# slush_cap_board_rev_a.net
KiCad netlist of a schematic drawn in EAGLE
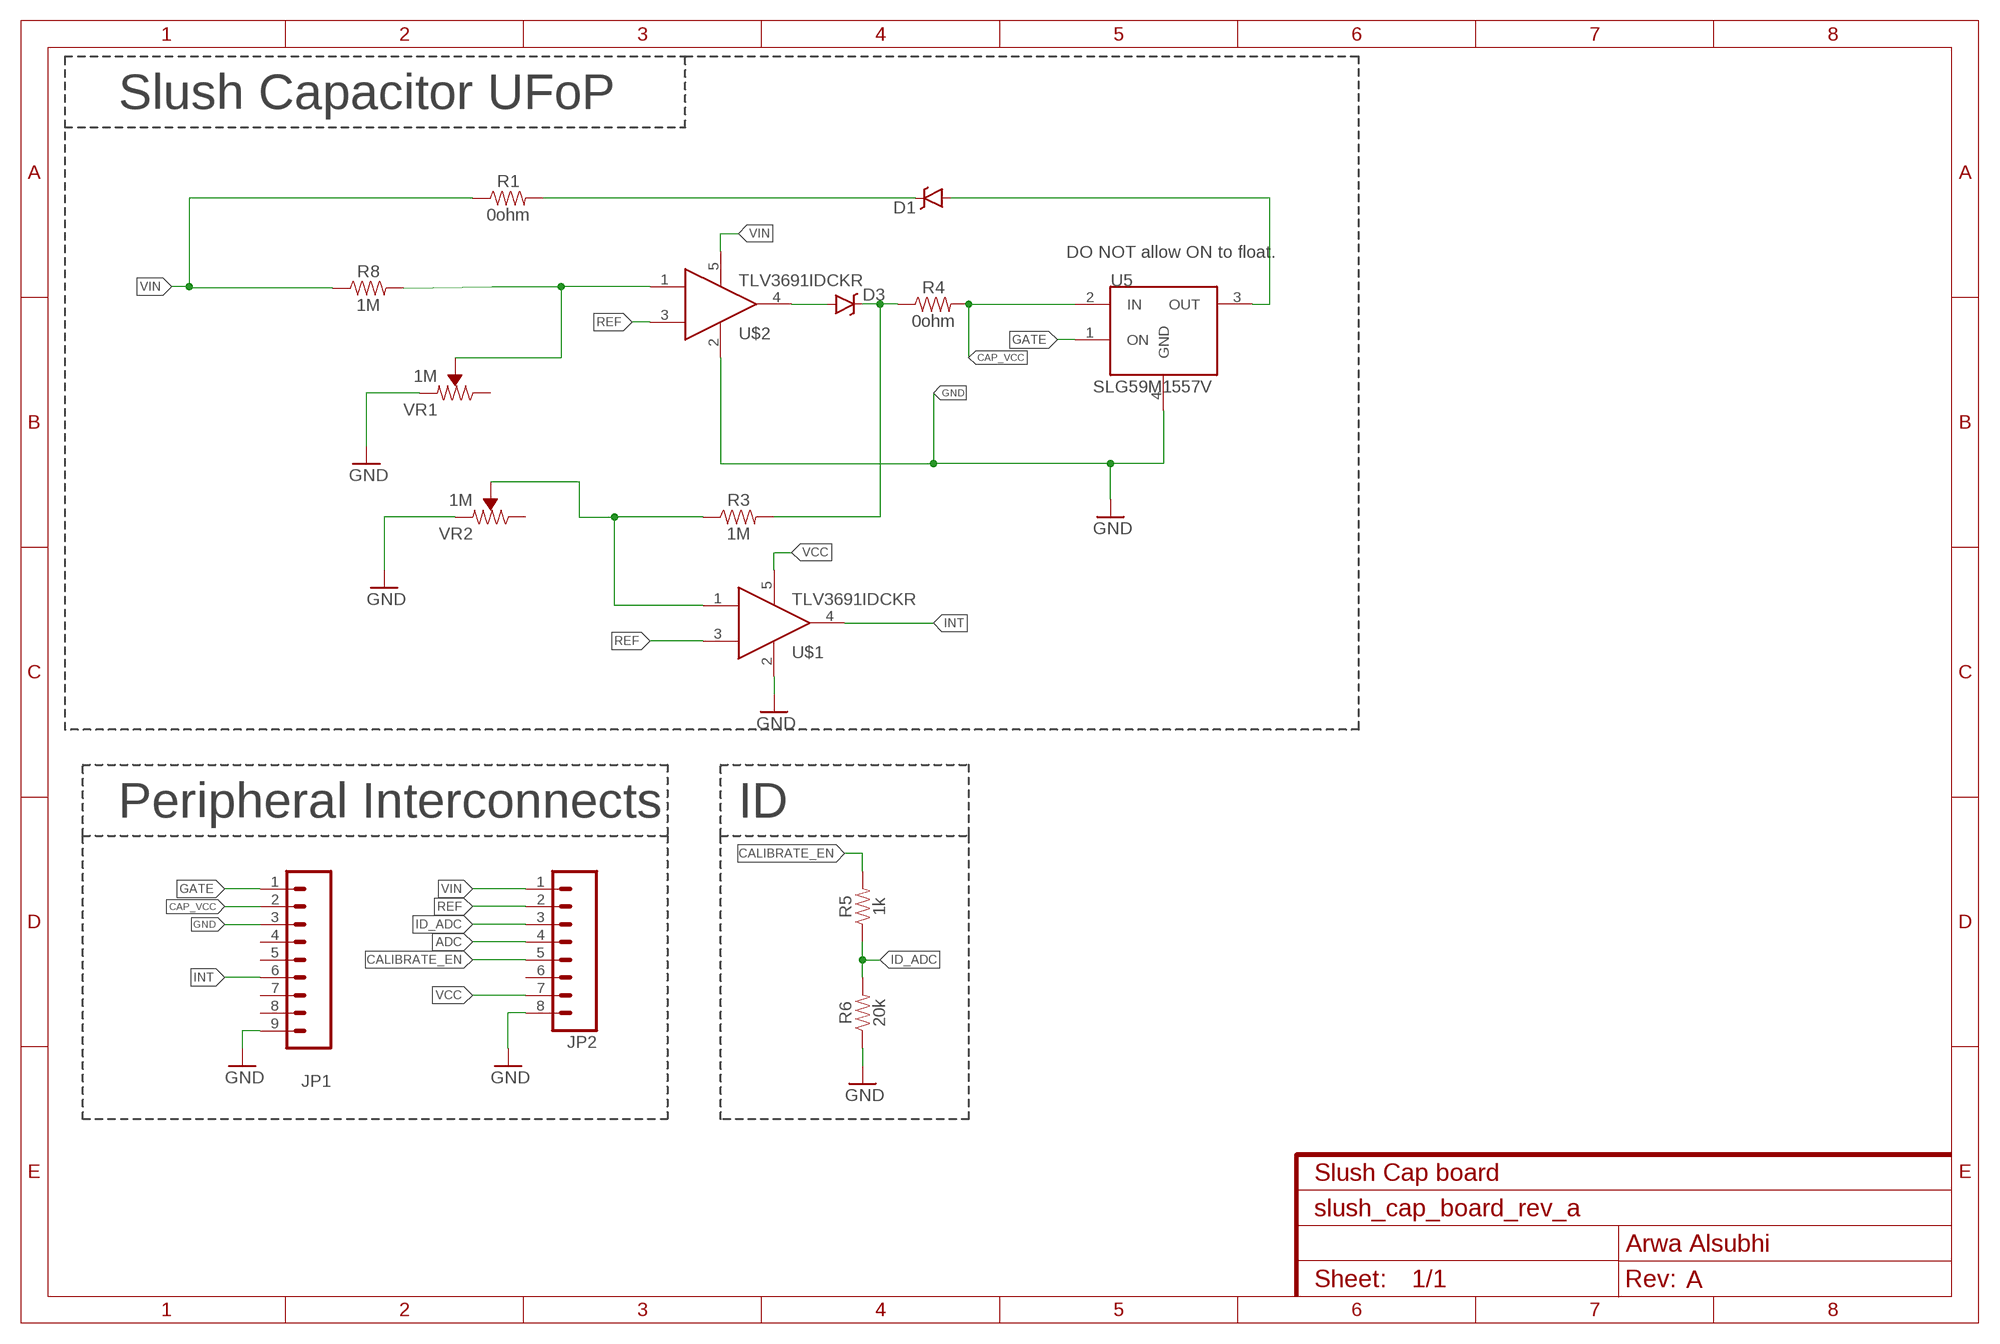
[diagram p0: schematic, sheet 1]

(export (version "E")
  (design (tool "Eeschema 10.0.6"))
  (components
    (comp (ref "D1")
      (value "RB751")
      (footprint "eagle-import:SOD-523")
      (fields (field (name "MPN") "BAS40-02V-V-G-08"))
      (libsource (lib "eagle-import") (part "DIODE-SCHOTTKY-RB751"))
    )
    (comp (ref "D3")
      (value "RB751")
      (footprint "eagle-import:SOD-523")
      (fields (field (name "MPN") "BAS40-02V-V-G-08"))
      (libsource (lib "eagle-import") (part "DIODE-SCHOTTKY-RB751"))
    )
    (comp (ref "JP1")
      (value "M091.27MM")
      (footprint "eagle-import:1X09-1.27MM")
      (fields (field (name "MANUFACTURERPARTNUMBER") "GRPB091VWVN-RC ") (field (name "MPN") "GRPB091VWVN-RC"))
      (libsource (lib "eagle-import") (part "M091.27MM"))
    )
    (comp (ref "JP2")
      (value "M081.27MM")
      (footprint "eagle-import:1X08-1.27MM")
      (fields (field (name "MANUFACTURERPARTNUMBER") "GRPB081VWVN-RC "))
      (libsource (lib "eagle-import") (part "M081.27MM"))
    )
    (comp (ref "R1")
      (value "0ohm")
      (footprint "eagle-import:0603")
      (libsource (lib "eagle-import") (part "0603-RESISTOR-0603-1/10W-1%"))
    )
    (comp (ref "R3")
      (value "1M")
      (footprint "eagle-import:0805")
      (libsource (lib "eagle-import") (part "0.3OHM-0805-1/8W-1%"))
    )
    (comp (ref "R4")
      (value "0ohm")
      (footprint "eagle-import:0603")
      (libsource (lib "eagle-import") (part "0603-RESISTOR-0603-1/10W-1%"))
    )
    (comp (ref "R5")
      (value "1k")
      (footprint "eagle-import:0603")
      (libsource (lib "eagle-import") (part "0603-RESISTOR-0603-1/10W-1%"))
    )
    (comp (ref "R6")
      (value "20k")
      (footprint "eagle-import:0603")
      (libsource (lib "eagle-import") (part "0603-RESISTOR-0603-1/10W-1%"))
    )
    (comp (ref "R8")
      (value "1M")
      (footprint "eagle-import:0805")
      (libsource (lib "eagle-import") (part "0.3OHM-0805-1/8W-1%"))
    )
    (comp (ref "U$1")
      (value "TLV3691IDCKR")
      (footprint "eagle-import:SOT353")
      (libsource (lib "eagle-import") (part "TLV3691IDCKR"))
    )
    (comp (ref "U$2")
      (value "TLV3691IDCKR")
      (footprint "eagle-import:SOT353")
      (libsource (lib "eagle-import") (part "TLV3691IDCKR"))
    )
    (comp (ref "U5")
      (value "SLG59M1557V")
      (footprint "eagle-import:4STDFN")
      (fields (field (name "MPN") "SLG59M1557V "))
      (libsource (lib "eagle-import") (part "SLG59M1557V"))
    )
    (comp (ref "VR1")
      (value "1M")
      (footprint "eagle-import:TRIMPOT-SMD-3MM-CLOSED")
      (libsource (lib "eagle-import") (part "TRIMPOT-SMD-3MM-CLOSED-1/8W-20%"))
    )
    (comp (ref "VR2")
      (value "1M")
      (footprint "eagle-import:TRIMPOT-SMD-3MM-CLOSED")
      (libsource (lib "eagle-import") (part "TRIMPOT-SMD-3MM-CLOSED-1/8W-20%"))
    )
  )
  (nets
    (net (code "1") (name "ADC") (class "Default")
      (node (ref "JP2") (pin "4") (pinfunction "4_4") (pintype "passive"))
    )
    (net (code "2") (name "CALIBRATE_EN") (class "Default")
      (node (ref "JP2") (pin "5") (pinfunction "5_5") (pintype "passive"))
      (node (ref "R5") (pin "2") (pinfunction "2_2") (pintype "passive"))
    )
    (net (code "3") (name "CAP_VCC") (class "Default")
      (node (ref "JP1") (pin "2") (pinfunction "2_2") (pintype "passive"))
      (node (ref "R4") (pin "2") (pinfunction "2_2") (pintype "passive"))
      (node (ref "U5") (pin "2") (pinfunction "IN_2") (pintype "bidirectional"))
    )
    (net (code "4") (name "GATE") (class "Default")
      (node (ref "JP1") (pin "1") (pinfunction "1_1") (pintype "passive"))
      (node (ref "U5") (pin "1") (pinfunction "ON_1") (pintype "bidirectional"))
    )
    (net (code "5") (name "GND") (class "Default")
      (node (ref "JP1") (pin "3") (pinfunction "3_3") (pintype "passive"))
      (node (ref "JP1") (pin "9") (pinfunction "9_9") (pintype "passive"))
      (node (ref "JP2") (pin "8") (pinfunction "8_8") (pintype "passive"))
      (node (ref "R6") (pin "1") (pinfunction "1_1") (pintype "passive"))
      (node (ref "U$1") (pin "2") (pinfunction "2_2") (pintype "bidirectional"))
      (node (ref "U$2") (pin "2") (pinfunction "2_2") (pintype "bidirectional"))
      (node (ref "U5") (pin "4") (pinfunction "GND_4") (pintype "bidirectional"))
      (node (ref "VR1") (pin "1") (pinfunction "CCW_1") (pintype "passive"))
      (node (ref "VR2") (pin "1") (pinfunction "CCW_1") (pintype "passive"))
    )
    (net (code "6") (name "ID_ADC") (class "Default")
      (node (ref "JP2") (pin "3") (pinfunction "3_3") (pintype "passive"))
      (node (ref "R5") (pin "1") (pinfunction "1_1") (pintype "passive"))
      (node (ref "R6") (pin "2") (pinfunction "2_2") (pintype "passive"))
    )
    (net (code "7") (name "INT") (class "Default")
      (node (ref "JP1") (pin "6") (pinfunction "6_6") (pintype "passive"))
      (node (ref "U$1") (pin "4") (pinfunction "4_4") (pintype "bidirectional"))
    )
    (net (code "8") (name "Net-(D1-PadC)") (class "Default")
      (node (ref "D1") (pin "C") (pinfunction "C_C") (pintype "passive"))
      (node (ref "R1") (pin "2") (pinfunction "2_2") (pintype "passive"))
    )
    (net (code "9") (name "Net-(D3-PadA)") (class "Default")
      (node (ref "D3") (pin "A") (pinfunction "A_A") (pintype "passive"))
      (node (ref "U$2") (pin "4") (pinfunction "4_4") (pintype "bidirectional"))
    )
    (net (code "10") (name "Net-(D3-PadC)") (class "Default")
      (node (ref "D3") (pin "C") (pinfunction "C_C") (pintype "passive"))
      (node (ref "R3") (pin "2") (pinfunction "2_2") (pintype "passive"))
      (node (ref "R4") (pin "1") (pinfunction "1_1") (pintype "passive"))
    )
    (net (code "11") (name "Net-(U5-OUT)") (class "Default")
      (node (ref "D1") (pin "A") (pinfunction "A_A") (pintype "passive"))
      (node (ref "U5") (pin "3") (pinfunction "OUT_3") (pintype "bidirectional"))
    )
    (net (code "12") (name "Net-(VR1-WIPER)") (class "Default")
      (node (ref "R8") (pin "2") (pinfunction "2_2") (pintype "passive"))
      (node (ref "U$2") (pin "1") (pinfunction "1_1") (pintype "bidirectional"))
      (node (ref "VR1") (pin "2") (pinfunction "WIPER_2") (pintype "passive"))
    )
    (net (code "13") (name "Net-(VR2-WIPER)") (class "Default")
      (node (ref "R3") (pin "1") (pinfunction "1_1") (pintype "passive"))
      (node (ref "U$1") (pin "1") (pinfunction "1_1") (pintype "bidirectional"))
      (node (ref "VR2") (pin "2") (pinfunction "WIPER_2") (pintype "passive"))
    )
    (net (code "14") (name "REF") (class "Default")
      (node (ref "JP2") (pin "2") (pinfunction "2_2") (pintype "passive"))
      (node (ref "U$1") (pin "3") (pinfunction "3_3") (pintype "bidirectional"))
      (node (ref "U$2") (pin "3") (pinfunction "3_3") (pintype "bidirectional"))
    )
    (net (code "15") (name "VCC") (class "Default")
      (node (ref "JP2") (pin "7") (pinfunction "7_7") (pintype "passive"))
      (node (ref "U$1") (pin "5") (pinfunction "5_5") (pintype "bidirectional"))
    )
    (net (code "16") (name "VIN") (class "Default")
      (node (ref "JP2") (pin "1") (pinfunction "1_1") (pintype "passive"))
      (node (ref "R1") (pin "1") (pinfunction "1_1") (pintype "passive"))
      (node (ref "R8") (pin "1") (pinfunction "1_1") (pintype "passive"))
      (node (ref "U$2") (pin "5") (pinfunction "5_5") (pintype "bidirectional"))
    )
    (net (code "17") (name "unconnected-(JP1-Pad4)") (class "Default")
      (node (ref "JP1") (pin "4") (pinfunction "4_4") (pintype "passive"))
    )
    (net (code "18") (name "unconnected-(JP1-Pad5)") (class "Default")
      (node (ref "JP1") (pin "5") (pinfunction "5_5") (pintype "passive"))
    )
    (net (code "19") (name "unconnected-(JP1-Pad7)") (class "Default")
      (node (ref "JP1") (pin "7") (pinfunction "7_7") (pintype "passive"))
    )
    (net (code "20") (name "unconnected-(JP1-Pad8)") (class "Default")
      (node (ref "JP1") (pin "8") (pinfunction "8_8") (pintype "passive"))
    )
    (net (code "21") (name "unconnected-(JP2-Pad6)") (class "Default")
      (node (ref "JP2") (pin "6") (pinfunction "6_6") (pintype "passive"))
    )
    (net (code "22") (name "unconnected-(VR1-CW-Pad3)") (class "Default")
      (node (ref "VR1") (pin "3") (pinfunction "CW_3") (pintype "passive"))
    )
    (net (code "23") (name "unconnected-(VR2-CW-Pad3)") (class "Default")
      (node (ref "VR2") (pin "3") (pinfunction "CW_3") (pintype "passive"))
    )
  )
)
